# 8_-_DAC_and_MIC.net
KiCad netlist of a schematic drawn in Altium Designer
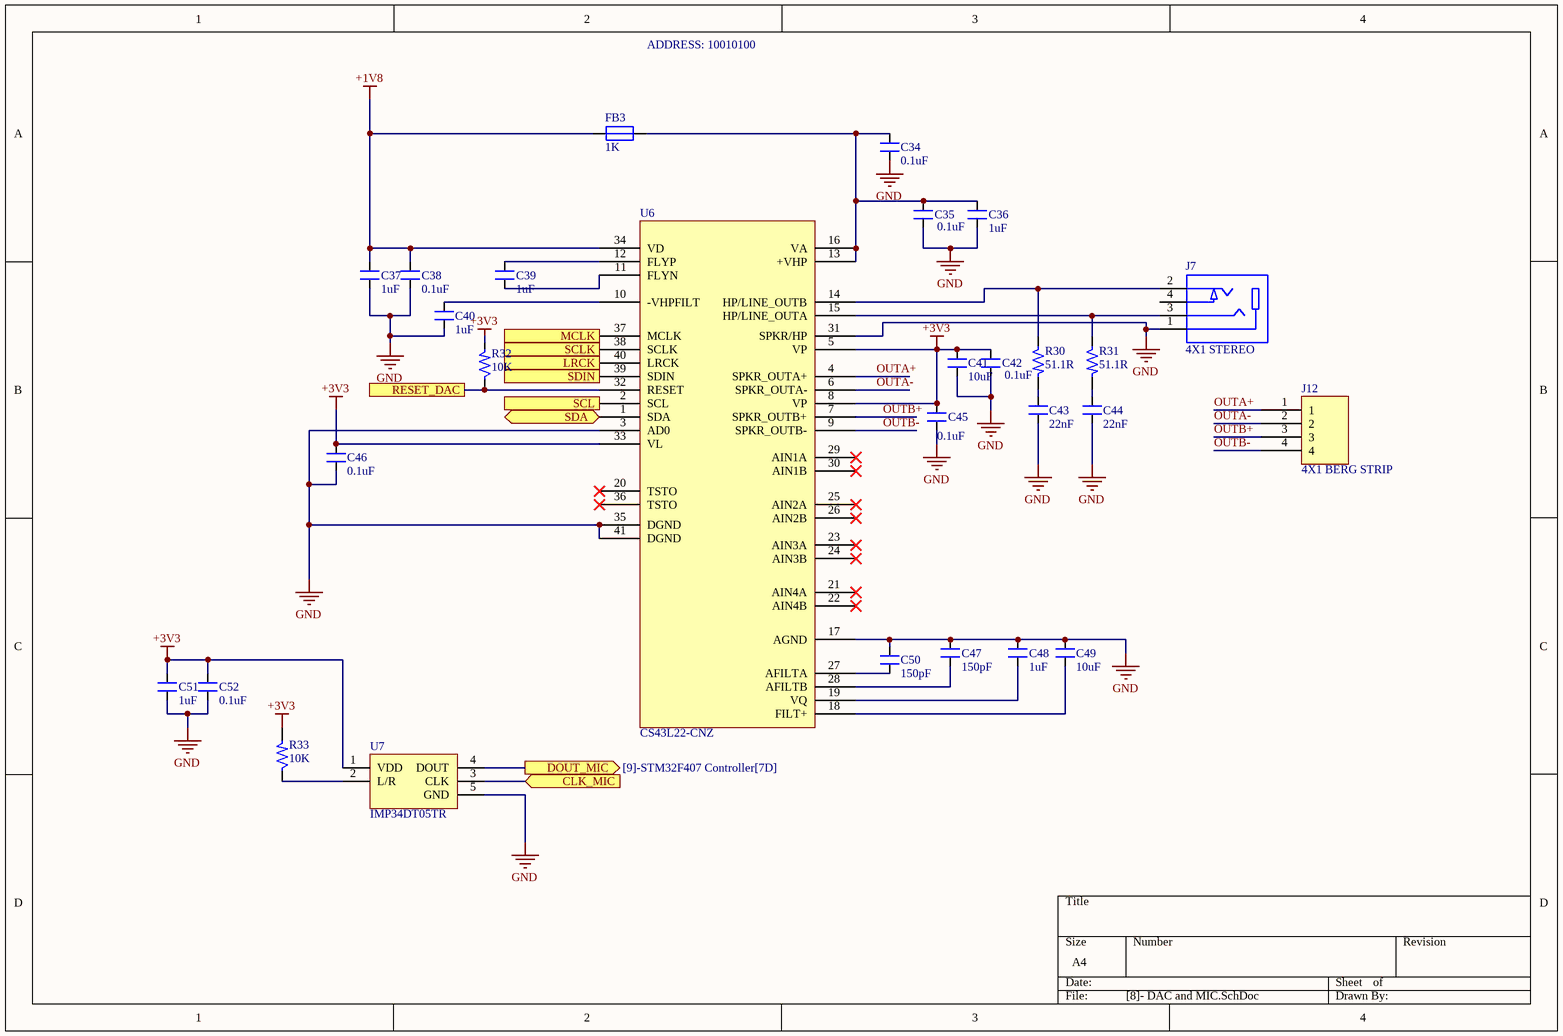
[diagram p0: [8]- DAC and MIC.SchDoc]

(export (version "E")
  (design (tool "Eeschema 10.0.6"))
  (components
    (comp (ref "C34")
      (value "0.1uF")
      (footprint "CAP_0805")
      (description "0.1µF ±10% 50V Ceramic Capacitor X7R 0805 (2012 Metric)")
      (fields
        (field (name "MANUFACTURER") "Samsung")
        (field (name "MANUFACTURER PART NUMBER") "CL21B104KBCNNNC")
      )
      (libsource (lib "ESTEEMPCBLIB") (part "CAP_0.1uF-50V-10%-0805"))
    )
    (comp (ref "C35")
      (value "0.1uF")
      (footprint "CAP_0805")
      (description "0.1µF ±10% 50V Ceramic Capacitor X7R 0805 (2012 Metric)")
      (fields
        (field (name "MANUFACTURER") "Samsung")
        (field (name "MANUFACTURER PART NUMBER") "CL21B104KBCNNNC")
      )
      (libsource (lib "ESTEEMPCBLIB") (part "CAP_0.1uF-50V-10%-0805"))
    )
    (comp (ref "C36")
      (value "1uF")
      (footprint "CAP_0805")
      (description "1µF ±5% 50V Ceramic Capacitor X7R 0805 (2012 Metric)")
      (fields
        (field (name "MANUFACTURER") "Samsung")
        (field (name "MANUFACTURER PART NUMBER") "CC0805JKX7R9BB105")
      )
      (libsource (lib "ESTEEMPCBLIB") (part "CAP_1uF-50V-5%-0805"))
    )
    (comp (ref "C37")
      (value "1uF")
      (footprint "CAP_0805")
      (description "1µF ±5% 50V Ceramic Capacitor X7R 0805 (2012 Metric)")
      (fields
        (field (name "MANUFACTURER") "Samsung")
        (field (name "MANUFACTURER PART NUMBER") "CC0805JKX7R9BB105")
      )
      (libsource (lib "ESTEEMPCBLIB") (part "CAP_1uF-50V-5%-0805"))
    )
    (comp (ref "C38")
      (value "0.1uF")
      (footprint "CAP_0805")
      (description "0.1µF ±10% 50V Ceramic Capacitor X7R 0805 (2012 Metric)")
      (fields
        (field (name "MANUFACTURER") "Samsung")
        (field (name "MANUFACTURER PART NUMBER") "CL21B104KBCNNNC")
      )
      (libsource (lib "ESTEEMPCBLIB") (part "CAP_0.1uF-50V-10%-0805"))
    )
    (comp (ref "C39")
      (value "1uF")
      (footprint "CAP_0805")
      (description "1µF ±5% 50V Ceramic Capacitor X7R 0805 (2012 Metric)")
      (fields
        (field (name "MANUFACTURER") "Samsung")
        (field (name "MANUFACTURER PART NUMBER") "CC0805JKX7R9BB105")
      )
      (libsource (lib "ESTEEMPCBLIB") (part "CAP_1uF-50V-5%-0805"))
    )
    (comp (ref "C40")
      (value "1uF")
      (footprint "CAP_0805")
      (description "1µF ±5% 50V Ceramic Capacitor X7R 0805 (2012 Metric)")
      (fields
        (field (name "MANUFACTURER") "Samsung")
        (field (name "MANUFACTURER PART NUMBER") "CC0805JKX7R9BB105")
      )
      (libsource (lib "ESTEEMPCBLIB") (part "CAP_1uF-50V-5%-0805"))
    )
    (comp (ref "C41")
      (value "10uF")
      (footprint "CAP_1206")
      (description "10µF ±10% 50V Ceramic Capacitor X7R 1206 (3216 Metric)")
      (fields
        (field (name "MANUFACTURER") "KEMET")
        (field (name "MANUFACTURER PART NUMBER") "CL31B106KBHNNNE")
      )
      (libsource (lib "ESTEEMPCBLIB") (part "CAP_10uF-50V-10%-1206"))
    )
    (comp (ref "C42")
      (value "0.1uF")
      (footprint "CAP_0805")
      (description "0.1µF ±10% 50V Ceramic Capacitor X7R 0805 (2012 Metric)")
      (fields
        (field (name "MANUFACTURER") "Samsung")
        (field (name "MANUFACTURER PART NUMBER") "CL21B104KBCNNNC")
      )
      (libsource (lib "ESTEEMPCBLIB") (part "CAP_0.1uF-50V-10%-0805"))
    )
    (comp (ref "C43")
      (value "22nF")
      (footprint "CAP_0805")
      (description "0.022µF ±10% 50V Ceramic Capacitor X7R 0805 (2012 Metric)")
      (fields
        (field (name "MANUFACTURER") "Samsung Electro-Mechanics")
        (field (name "MANUFACTURER PART NUMBER") "CL21B223KBANNNC")
      )
      (libsource (lib "ESTEEMPCBLIB") (part "CAP_22nF-50V-10%-0805"))
    )
    (comp (ref "C44")
      (value "22nF")
      (footprint "CAP_0805")
      (description "0.022µF ±10% 50V Ceramic Capacitor X7R 0805 (2012 Metric)")
      (fields
        (field (name "MANUFACTURER") "Samsung Electro-Mechanics")
        (field (name "MANUFACTURER PART NUMBER") "CL21B223KBANNNC")
      )
      (libsource (lib "ESTEEMPCBLIB") (part "CAP_22nF-50V-10%-0805"))
    )
    (comp (ref "C45")
      (value "0.1uF")
      (footprint "CAP_0805")
      (description "0.1µF ±10% 50V Ceramic Capacitor X7R 0805 (2012 Metric)")
      (fields
        (field (name "MANUFACTURER") "Samsung")
        (field (name "MANUFACTURER PART NUMBER") "CL21B104KBCNNNC")
      )
      (libsource (lib "ESTEEMPCBLIB") (part "CAP_0.1uF-50V-10%-0805"))
    )
    (comp (ref "C46")
      (value "0.1uF")
      (footprint "CAP_0805")
      (description "0.1µF ±10% 50V Ceramic Capacitor X7R 0805 (2012 Metric)")
      (fields
        (field (name "MANUFACTURER") "Samsung")
        (field (name "MANUFACTURER PART NUMBER") "CL21B104KBCNNNC")
      )
      (libsource (lib "ESTEEMPCBLIB") (part "CAP_0.1uF-50V-10%-0805"))
    )
    (comp (ref "C47")
      (value "150pF")
      (footprint "CAP_0805")
      (description "150pF ±10% 50V Ceramic Capacitor C0G, NP0 0805 (2012 Metric)")
      (fields
        (field (name "MANUFACTURER") "AVX Corporation")
        (field (name "MANUFACTURER PART NUMBER") "08055A151KAT2A")
      )
      (libsource (lib "ESTEEMPCBLIB") (part "CAP_150pF-50V-10%-0805"))
    )
    (comp (ref "C48")
      (value "1uF")
      (footprint "CAP_0805")
      (description "1µF ±5% 50V Ceramic Capacitor X7R 0805 (2012 Metric)")
      (fields
        (field (name "MANUFACTURER") "Samsung")
        (field (name "MANUFACTURER PART NUMBER") "CC0805JKX7R9BB105")
      )
      (libsource (lib "ESTEEMPCBLIB") (part "CAP_1uF-50V-5%-0805"))
    )
    (comp (ref "C49")
      (value "10uF")
      (footprint "CAP_1206")
      (description "10µF ±10% 50V Ceramic Capacitor X7R 1206 (3216 Metric)")
      (fields
        (field (name "MANUFACTURER") "KEMET")
        (field (name "MANUFACTURER PART NUMBER") "CL31B106KBHNNNE")
      )
      (libsource (lib "ESTEEMPCBLIB") (part "CAP_10uF-50V-10%-1206"))
    )
    (comp (ref "C50")
      (value "150pF")
      (footprint "CAP_0805")
      (description "150pF ±10% 50V Ceramic Capacitor C0G, NP0 0805 (2012 Metric)")
      (fields
        (field (name "MANUFACTURER") "AVX Corporation")
        (field (name "MANUFACTURER PART NUMBER") "08055A151KAT2A")
      )
      (libsource (lib "ESTEEMPCBLIB") (part "CAP_150pF-50V-10%-0805"))
    )
    (comp (ref "C51")
      (value "1uF")
      (footprint "CAP_0805")
      (description "1µF ±5% 50V Ceramic Capacitor X7R 0805 (2012 Metric)")
      (fields
        (field (name "MANUFACTURER") "Samsung")
        (field (name "MANUFACTURER PART NUMBER") "CC0805JKX7R9BB105")
      )
      (libsource (lib "ESTEEMPCBLIB") (part "CAP_1uF-50V-5%-0805"))
    )
    (comp (ref "C52")
      (value "0.1uF")
      (footprint "CAP_0805")
      (description "0.1µF ±10% 50V Ceramic Capacitor X7R 0805 (2012 Metric)")
      (fields
        (field (name "MANUFACTURER") "Samsung")
        (field (name "MANUFACTURER PART NUMBER") "CL21B104KBCNNNC")
      )
      (libsource (lib "ESTEEMPCBLIB") (part "CAP_0.1uF-50V-10%-0805"))
    )
    (comp (ref "FB3")
      (value "1K")
      (footprint "IND_0805")
      (description "1 kOhms @ 100MHz 1 Power Line Ferrite Bead 0805 (2012 Metric) 1.6A")
      (fields
        (field (name "MANUFACTURER") "Laird")
        (field (name "MANUFACTURER PART NUMBER") "BLM21SP102SH1D")
      )
      (libsource (lib "ESTEEMPCBLIB") (part "FB_1K-100MHZ-1.6A-0805"))
    )
    (comp (ref "J7")
      (value "4X1 STEREO")
      (footprint "CON_SJ-2504A-SMT-TR_SMD")
      (fields
        (field (name "MANUFACTURER") "CUI Devices")
        (field (name "MANUFACTURER PART NUMBER") "SJ-2504A-SMT-TR")
      )
      (libsource (lib "ESTEEMPCBLIB") (part "CON-PLG-STEREO_4X1-100-RA-SMD"))
    )
    (comp (ref "J12")
      (value "4X1 BERG STRIP")
      (footprint "CON4_100_40D72_TH_ST_MALE")
      (description "4 Pins, 1 Row 2.54mm Pitch, Straight bergstrip, Male")
      (fields (field (name "MANUFACTURER") "NA"))
      (libsource (lib "ESTEEMPCBLIB") (part "CON-BS-PLG_4X1-100-ST-TH"))
    )
    (comp (ref "R30")
      (value "51.1R")
      (footprint "RES_0603")
      (description "51.1 Ohms ±1% 0.1W, 1/10W Chip Resistor 0603 (1608 Metric) Thick Film")
      (fields
        (field (name "MANUFACTURER") "Vishay Dale")
        (field (name "MANUFACTURER PART NUMBER") "CRCW060351R1FKEAC")
      )
      (libsource (lib "ESTEEMPCBLIB") (part "RES_51.1R-0.1W-1%-0603"))
    )
    (comp (ref "R31")
      (value "51.1R")
      (footprint "RES_0603")
      (description "51.1 Ohms ±1% 0.1W, 1/10W Chip Resistor 0603 (1608 Metric) Thick Film")
      (fields
        (field (name "MANUFACTURER") "Vishay Dale")
        (field (name "MANUFACTURER PART NUMBER") "CRCW060351R1FKEAC")
      )
      (libsource (lib "ESTEEMPCBLIB") (part "RES_51.1R-0.1W-1%-0603"))
    )
    (comp (ref "R32")
      (value "10K")
      (footprint "RES_0603")
      (description "10 kOhms ±1% 0.1W, 1/10W Chip Resistor 0603 (1608 Metric) Automotive AEC-Q200 Thick Film")
      (fields (field (name "MANUFACTURER") "Walsin") (field (name "MANUFACTURER PART NUMBER") "WR06X1002FTL"))
      (libsource (lib "ESTEEMPCBLIB") (part "RES_10K-0.1W-1%-0603"))
    )
    (comp (ref "R33")
      (value "10K")
      (footprint "RES_0603")
      (description "10 kOhms ±1% 0.1W, 1/10W Chip Resistor 0603 (1608 Metric) Automotive AEC-Q200 Thick Film")
      (fields (field (name "MANUFACTURER") "Walsin") (field (name "MANUFACTURER PART NUMBER") "WR06X1002FTL"))
      (libsource (lib "ESTEEMPCBLIB") (part "RES_10K-0.1W-1%-0603"))
    )
    (comp (ref "U6")
      (value "CS43L22-CNZ")
      (footprint "QFN40_19_284_33X9_SMD")
      (description "Audio D/A Converter ICs Low Power Stereo DAC w/ClassD Spkr Driver")
      (fields (field (name "MANUFACTURER") "Cirrus Logic"))
      (libsource (lib "ESTEEMPCBLIB") (part "IC_CS43L22"))
    )
    (comp (ref "U7")
      (value "IMP34DT05TR")
      (footprint "HCLGA-4_53_137_15X37_SMD")
      (description "MEMS Microphones AUTO & INDUSTRIAL SENSORS")
      (fields (field (name "MANUFACTURER") "STMicroelectronics"))
      (libsource (lib "ESTEEMPCBLIB") (part "IC_IMP34DT05TR"))
    )
  )
  (nets
    (net (code "1") (name "+1V8") (class "Default")
      (node (ref "C37") (pin "2") (pinfunction "2_2") (pintype "passive"))
      (node (ref "C38") (pin "2") (pinfunction "2_2") (pintype "passive"))
      (node (ref "FB3") (pin "1") (pinfunction "1_1") (pintype "passive"))
      (node (ref "U6") (pin "34") (pinfunction "VD_34") (pintype "passive"))
    )
    (net (code "2") (name "+3V3") (class "Default")
      (node (ref "C41") (pin "2") (pinfunction "2_2") (pintype "passive"))
      (node (ref "C42") (pin "2") (pinfunction "2_2") (pintype "passive"))
      (node (ref "C45") (pin "2") (pinfunction "2_2") (pintype "passive"))
      (node (ref "C46") (pin "2") (pinfunction "2_2") (pintype "passive"))
      (node (ref "C51") (pin "2") (pinfunction "2_2") (pintype "passive"))
      (node (ref "C52") (pin "2") (pinfunction "2_2") (pintype "passive"))
      (node (ref "R32") (pin "2") (pinfunction "2_2") (pintype "passive"))
      (node (ref "R33") (pin "2") (pinfunction "2_2") (pintype "passive"))
      (node (ref "U6") (pin "33") (pinfunction "VL_33") (pintype "passive"))
      (node (ref "U6") (pin "5") (pinfunction "VP_5") (pintype "passive"))
      (node (ref "U6") (pin "8") (pinfunction "VP_8") (pintype "passive"))
      (node (ref "U7") (pin "1") (pinfunction "VDD_1") (pintype "passive"))
    )
    (net (code "3") (name "/CLK_MIC") (class "Default")
      (node (ref "U7") (pin "3") (pinfunction "CLK_3") (pintype "passive"))
    )
    (net (code "4") (name "/DOUT_MIC") (class "Default")
      (node (ref "U7") (pin "4") (pinfunction "DOUT_4") (pintype "passive"))
    )
    (net (code "5") (name "/LRCK") (class "Default")
      (node (ref "U6") (pin "40") (pinfunction "LRCK_40") (pintype "passive"))
    )
    (net (code "6") (name "/MCLK") (class "Default")
      (node (ref "U6") (pin "37") (pinfunction "MCLK_37") (pintype "passive"))
    )
    (net (code "7") (name "/OUTA+") (class "Default")
      (node (ref "J12") (pin "1") (pinfunction "1_1") (pintype "passive"))
      (node (ref "U6") (pin "4") (pinfunction "SPKR_OUTA+_4") (pintype "passive"))
    )
    (net (code "8") (name "/OUTA-") (class "Default")
      (node (ref "J12") (pin "2") (pinfunction "2_2") (pintype "passive"))
      (node (ref "U6") (pin "6") (pinfunction "SPKR_OUTA-_6") (pintype "passive"))
    )
    (net (code "9") (name "/OUTB+") (class "Default")
      (node (ref "J12") (pin "3") (pinfunction "3_3") (pintype "passive"))
      (node (ref "U6") (pin "7") (pinfunction "SPKR_OUTB+_7") (pintype "passive"))
    )
    (net (code "10") (name "/OUTB-") (class "Default")
      (node (ref "J12") (pin "4") (pinfunction "4_4") (pintype "passive"))
      (node (ref "U6") (pin "9") (pinfunction "SPKR_OUTB-_9") (pintype "passive"))
    )
    (net (code "11") (name "/RESET_DAC") (class "Default")
      (node (ref "R32") (pin "1") (pinfunction "1_1") (pintype "passive"))
      (node (ref "U6") (pin "32") (pinfunction "RESET_32") (pintype "passive"))
    )
    (net (code "12") (name "/SCL") (class "Default")
      (node (ref "U6") (pin "2") (pinfunction "SCL_2") (pintype "passive"))
    )
    (net (code "13") (name "/SCLK") (class "Default")
      (node (ref "U6") (pin "38") (pinfunction "SCLK_38") (pintype "passive"))
    )
    (net (code "14") (name "/SDA") (class "Default")
      (node (ref "U6") (pin "1") (pinfunction "SDA_1") (pintype "passive"))
    )
    (net (code "15") (name "/SDIN") (class "Default")
      (node (ref "U6") (pin "39") (pinfunction "SDIN_39") (pintype "passive"))
    )
    (net (code "16") (name "GND") (class "Default")
      (node (ref "C34") (pin "1") (pinfunction "1_1") (pintype "passive"))
      (node (ref "C35") (pin "1") (pinfunction "1_1") (pintype "passive"))
      (node (ref "C36") (pin "1") (pinfunction "1_1") (pintype "passive"))
      (node (ref "C37") (pin "1") (pinfunction "1_1") (pintype "passive"))
      (node (ref "C38") (pin "1") (pinfunction "1_1") (pintype "passive"))
      (node (ref "C40") (pin "1") (pinfunction "1_1") (pintype "passive"))
      (node (ref "C41") (pin "1") (pinfunction "1_1") (pintype "passive"))
      (node (ref "C42") (pin "1") (pinfunction "1_1") (pintype "passive"))
      (node (ref "C43") (pin "2") (pinfunction "2_2") (pintype "passive"))
      (node (ref "C44") (pin "1") (pinfunction "1_1") (pintype "passive"))
      (node (ref "C45") (pin "1") (pinfunction "1_1") (pintype "passive"))
      (node (ref "C46") (pin "1") (pinfunction "1_1") (pintype "passive"))
      (node (ref "C47") (pin "2") (pinfunction "2_2") (pintype "passive"))
      (node (ref "C48") (pin "2") (pinfunction "2_2") (pintype "passive"))
      (node (ref "C49") (pin "2") (pinfunction "2_2") (pintype "passive"))
      (node (ref "C50") (pin "2") (pinfunction "2_2") (pintype "passive"))
      (node (ref "C51") (pin "1") (pinfunction "1_1") (pintype "passive"))
      (node (ref "C52") (pin "1") (pinfunction "1_1") (pintype "passive"))
      (node (ref "J7") (pin "1") (pinfunction "1_1") (pintype "passive"))
      (node (ref "U6") (pin "17") (pinfunction "AGND_17") (pintype "passive"))
      (node (ref "U6") (pin "3") (pinfunction "AD0_3") (pintype "passive"))
      (node (ref "U6") (pin "31") (pinfunction "SPKR/HP_31") (pintype "passive"))
      (node (ref "U6") (pin "35") (pinfunction "DGND_35") (pintype "passive"))
      (node (ref "U6") (pin "41") (pinfunction "DGND_41") (pintype "passive"))
      (node (ref "U7") (pin "5") (pinfunction "GND_5") (pintype "passive"))
    )
    (net (code "17") (name "Net-(C43-Pad1)") (class "Default")
      (node (ref "C43") (pin "1") (pinfunction "1_1") (pintype "passive"))
      (node (ref "R30") (pin "2") (pinfunction "2_2") (pintype "passive"))
    )
    (net (code "18") (name "Net-(C44-Pad2)") (class "Default")
      (node (ref "C44") (pin "2") (pinfunction "2_2") (pintype "passive"))
      (node (ref "R31") (pin "2") (pinfunction "2_2") (pintype "passive"))
    )
    (net (code "19") (name "Net-(U6-+VHP)") (class "Default")
      (node (ref "C34") (pin "2") (pinfunction "2_2") (pintype "passive"))
      (node (ref "C35") (pin "2") (pinfunction "2_2") (pintype "passive"))
      (node (ref "C36") (pin "2") (pinfunction "2_2") (pintype "passive"))
      (node (ref "FB3") (pin "2") (pinfunction "2_2") (pintype "passive"))
      (node (ref "U6") (pin "13") (pinfunction "+VHP_13") (pintype "passive"))
      (node (ref "U6") (pin "16") (pinfunction "VA_16") (pintype "passive"))
    )
    (net (code "20") (name "Net-(U6--VHPFILT)") (class "Default")
      (node (ref "C40") (pin "2") (pinfunction "2_2") (pintype "passive"))
      (node (ref "U6") (pin "10") (pinfunction "-VHPFILT_10") (pintype "passive"))
    )
    (net (code "21") (name "Net-(U6-AFILTA)") (class "Default")
      (node (ref "C50") (pin "1") (pinfunction "1_1") (pintype "passive"))
      (node (ref "U6") (pin "27") (pinfunction "AFILTA_27") (pintype "passive"))
    )
    (net (code "22") (name "Net-(U6-AFILTB)") (class "Default")
      (node (ref "C47") (pin "1") (pinfunction "1_1") (pintype "passive"))
      (node (ref "U6") (pin "28") (pinfunction "AFILTB_28") (pintype "passive"))
    )
    (net (code "23") (name "Net-(U6-FILT+)") (class "Default")
      (node (ref "C49") (pin "1") (pinfunction "1_1") (pintype "passive"))
      (node (ref "U6") (pin "18") (pinfunction "FILT+_18") (pintype "passive"))
    )
    (net (code "24") (name "Net-(U6-FLYN)") (class "Default")
      (node (ref "C39") (pin "1") (pinfunction "1_1") (pintype "passive"))
      (node (ref "U6") (pin "11") (pinfunction "FLYN_11") (pintype "passive"))
    )
    (net (code "25") (name "Net-(U6-FLYP)") (class "Default")
      (node (ref "C39") (pin "2") (pinfunction "2_2") (pintype "passive"))
      (node (ref "U6") (pin "12") (pinfunction "FLYP_12") (pintype "passive"))
    )
    (net (code "26") (name "Net-(U6-HP{slash}LINE_OUTA)") (class "Default")
      (node (ref "J7") (pin "3") (pinfunction "3_3") (pintype "passive"))
      (node (ref "R31") (pin "1") (pinfunction "1_1") (pintype "passive"))
      (node (ref "U6") (pin "15") (pinfunction "HP/LINE_OUTA_15") (pintype "passive"))
    )
    (net (code "27") (name "Net-(U6-HP{slash}LINE_OUTB)") (class "Default")
      (node (ref "J7") (pin "2") (pinfunction "2_2") (pintype "passive"))
      (node (ref "R30") (pin "1") (pinfunction "1_1") (pintype "passive"))
      (node (ref "U6") (pin "14") (pinfunction "HP/LINE_OUTB_14") (pintype "passive"))
    )
    (net (code "28") (name "Net-(U6-VQ)") (class "Default")
      (node (ref "C48") (pin "1") (pinfunction "1_1") (pintype "passive"))
      (node (ref "U6") (pin "19") (pinfunction "VQ_19") (pintype "passive"))
    )
    (net (code "29") (name "Net-(U7-L{slash}R)") (class "Default")
      (node (ref "R33") (pin "1") (pinfunction "1_1") (pintype "passive"))
      (node (ref "U7") (pin "2") (pinfunction "L/R_2") (pintype "passive"))
    )
    (net (code "30") (name "unconnected-(J7-Pad4)") (class "Default")
      (node (ref "J7") (pin "4") (pinfunction "4_4") (pintype "passive"))
    )
    (net (code "31") (name "unconnected-(U6-AIN1A-Pad29)") (class "Default")
      (node (ref "U6") (pin "29") (pinfunction "AIN1A_29") (pintype "passive+no_connect"))
    )
    (net (code "32") (name "unconnected-(U6-AIN1B-Pad30)") (class "Default")
      (node (ref "U6") (pin "30") (pinfunction "AIN1B_30") (pintype "passive+no_connect"))
    )
    (net (code "33") (name "unconnected-(U6-AIN2A-Pad25)") (class "Default")
      (node (ref "U6") (pin "25") (pinfunction "AIN2A_25") (pintype "passive+no_connect"))
    )
    (net (code "34") (name "unconnected-(U6-AIN2B-Pad26)") (class "Default")
      (node (ref "U6") (pin "26") (pinfunction "AIN2B_26") (pintype "passive+no_connect"))
    )
    (net (code "35") (name "unconnected-(U6-AIN3A-Pad23)") (class "Default")
      (node (ref "U6") (pin "23") (pinfunction "AIN3A_23") (pintype "passive+no_connect"))
    )
    (net (code "36") (name "unconnected-(U6-AIN3B-Pad24)") (class "Default")
      (node (ref "U6") (pin "24") (pinfunction "AIN3B_24") (pintype "passive+no_connect"))
    )
    (net (code "37") (name "unconnected-(U6-AIN4A-Pad21)") (class "Default")
      (node (ref "U6") (pin "21") (pinfunction "AIN4A_21") (pintype "passive+no_connect"))
    )
    (net (code "38") (name "unconnected-(U6-AIN4B-Pad22)") (class "Default")
      (node (ref "U6") (pin "22") (pinfunction "AIN4B_22") (pintype "passive+no_connect"))
    )
    (net (code "39") (name "unconnected-(U6-TSTO-Pad20)") (class "Default")
      (node (ref "U6") (pin "20") (pinfunction "TSTO_20") (pintype "passive+no_connect"))
    )
    (net (code "40") (name "unconnected-(U6-TSTO-Pad36)") (class "Default")
      (node (ref "U6") (pin "36") (pinfunction "TSTO_36") (pintype "passive+no_connect"))
    )
  )
)
